# Sheet1.net
KiCad netlist of a schematic drawn in Altium Designer
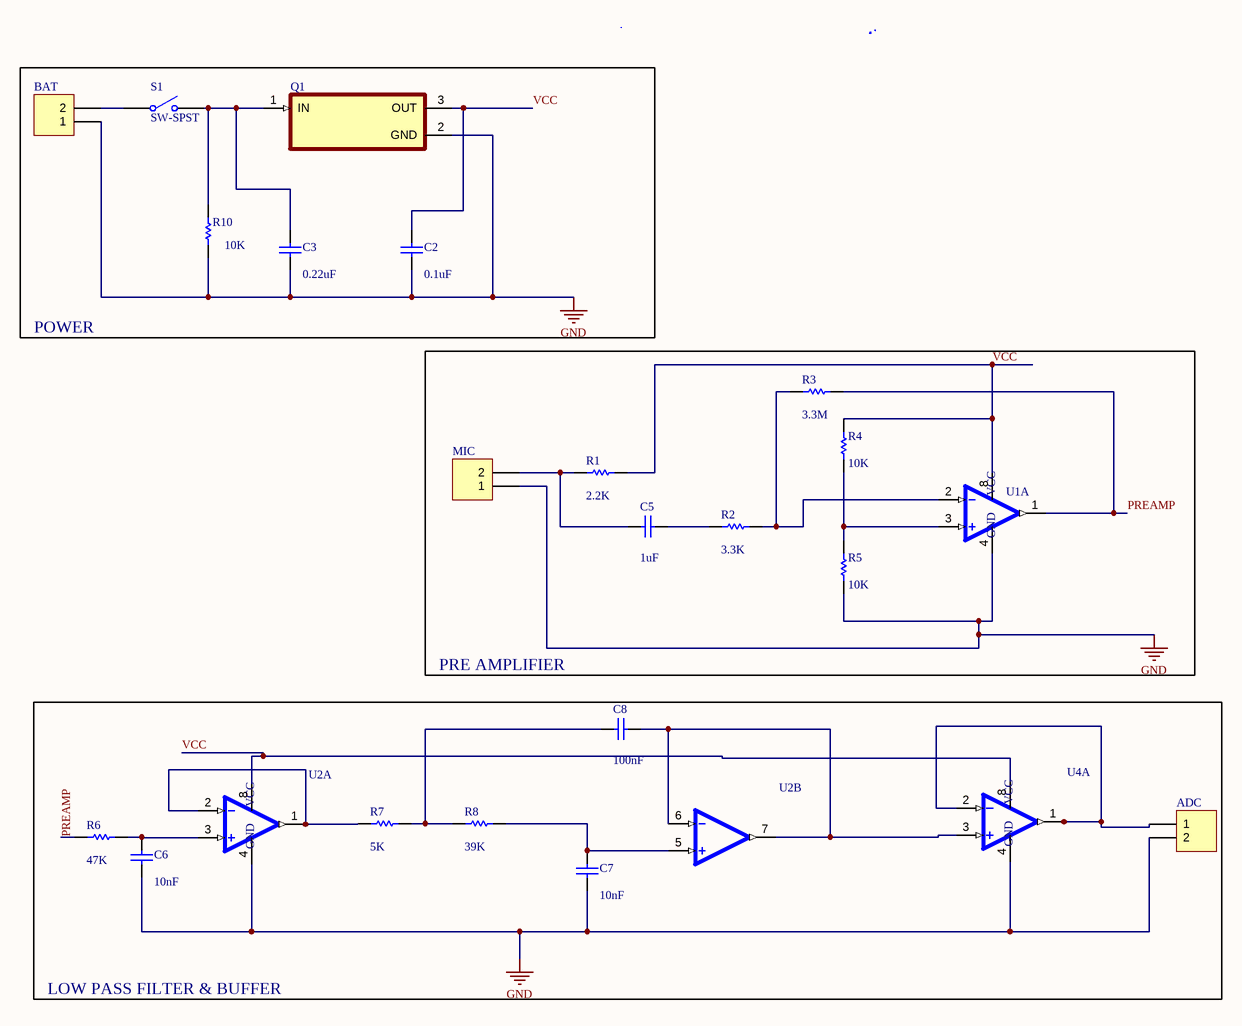
[diagram p0: Sheet1.SchDoc]

(export (version "E")
  (design (tool "Eeschema 10.0.6"))
  (components
    (comp (ref "ADC")
      (value "MHDR1X2")
      (footprint "MHDR1X2")
      (description "Header, 2-Pin")
      (fields (field (name "PUBLISHER") "Altium Limited"))
      (libsource (lib "Miscellaneous Connectors") (part "MHDR1X2"))
    )
    (comp (ref "BAT")
      (value "MHDR1X2")
      (footprint "MHDR1X2")
      (description "Header, 2-Pin")
      (fields (field (name "PUBLISHER") "Altium Limited"))
      (libsource (lib "") (part "MHDR1X2_1"))
    )
    (comp (ref "C2")
      (value "0.1uF")
      (footprint "RAD-0.3")
      (description "Capacitor")
      (fields (field (name "Comment") "Cap") (field (name "PUBLISHER") "Altium Limited"))
      (libsource (lib "Miscellaneous Devices") (part "Cap"))
    )
    (comp (ref "C3")
      (value "0.22uF")
      (footprint "RAD-0.3")
      (description "Capacitor")
      (fields (field (name "Comment") "Cap") (field (name "PUBLISHER") "Altium Limited"))
      (libsource (lib "Miscellaneous Devices") (part "Cap"))
    )
    (comp (ref "C5")
      (value "1uF")
      (footprint "RAD-0.3")
      (description "Capacitor")
      (fields (field (name "Comment") "Cap") (field (name "PUBLISHER") "Altium Limited"))
      (libsource (lib "Miscellaneous Devices") (part "Cap"))
    )
    (comp (ref "C6")
      (value "10nF")
      (footprint "RAD-0.3")
      (description "Capacitor")
      (fields (field (name "Comment") "Cap") (field (name "PUBLISHER") "Altium Limited"))
      (libsource (lib "Miscellaneous Devices") (part "Cap"))
    )
    (comp (ref "C7")
      (value "10nF")
      (footprint "RAD-0.3")
      (description "Capacitor")
      (fields (field (name "Comment") "Cap") (field (name "PUBLISHER") "Altium Limited"))
      (libsource (lib "Miscellaneous Devices") (part "Cap"))
    )
    (comp (ref "C8")
      (value "100nF")
      (footprint "RAD-0.3")
      (description "Capacitor")
      (fields (field (name "Comment") "Cap") (field (name "PUBLISHER") "Altium Limited"))
      (libsource (lib "Miscellaneous Devices") (part "Cap"))
    )
    (comp (ref "MIC")
      (value "MHDR1X2")
      (footprint "MHDR1X2")
      (description "Header, 2-Pin")
      (fields (field (name "PUBLISHER") "Altium Limited"))
      (libsource (lib "") (part "MHDR1X2_1"))
    )
    (comp (ref "Q1")
      (value "LM7805CT/NOPB")
      (footprint "TO254P1054X470X1955-3")
      (libsource (lib "LM7805CT_NOPB") (part "LM7805CT/NOPB"))
    )
    (comp (ref "R1")
      (value "2.2K")
      (footprint "AXIAL-0.3")
      (description "Resistor")
      (fields (field (name "Comment") "Res1") (field (name "PUBLISHER") "Altium Limited"))
      (libsource (lib "Miscellaneous Devices") (part "Res1"))
    )
    (comp (ref "R2")
      (value "3.3K")
      (footprint "AXIAL-0.3")
      (description "Resistor")
      (fields (field (name "Comment") "Res1") (field (name "PUBLISHER") "Altium Limited"))
      (libsource (lib "Miscellaneous Devices") (part "Res1"))
    )
    (comp (ref "R3")
      (value "3.3M")
      (footprint "AXIAL-0.3")
      (description "Resistor")
      (fields (field (name "Comment") "Res1") (field (name "PUBLISHER") "Altium Limited"))
      (libsource (lib "Miscellaneous Devices") (part "Res1"))
    )
    (comp (ref "R4")
      (value "10K")
      (footprint "AXIAL-0.3")
      (description "Resistor")
      (fields (field (name "Comment") "Res1") (field (name "PUBLISHER") "Altium Limited"))
      (libsource (lib "Miscellaneous Devices") (part "Res1"))
    )
    (comp (ref "R5")
      (value "10K")
      (footprint "AXIAL-0.3")
      (description "Resistor")
      (fields (field (name "Comment") "Res1") (field (name "PUBLISHER") "Altium Limited"))
      (libsource (lib "Miscellaneous Devices") (part "Res1"))
    )
    (comp (ref "R6")
      (value "47K")
      (footprint "AXIAL-0.3")
      (description "Resistor")
      (fields (field (name "Comment") "Res1") (field (name "PUBLISHER") "Altium Limited"))
      (libsource (lib "Miscellaneous Devices") (part "Res1"))
    )
    (comp (ref "R7")
      (value "5K")
      (footprint "AXIAL-0.3")
      (description "Resistor")
      (fields (field (name "Comment") "Res1") (field (name "PUBLISHER") "Altium Limited"))
      (libsource (lib "Miscellaneous Devices") (part "Res1"))
    )
    (comp (ref "R8")
      (value "39K")
      (footprint "AXIAL-0.3")
      (description "Resistor")
      (fields (field (name "Comment") "Res1") (field (name "PUBLISHER") "Altium Limited"))
      (libsource (lib "Miscellaneous Devices") (part "Res1"))
    )
    (comp (ref "R10")
      (value "10K")
      (footprint "AXIAL-0.3")
      (description "Resistor")
      (fields (field (name "Comment") "Res1") (field (name "PUBLISHER") "Altium Limited"))
      (libsource (lib "Miscellaneous Devices") (part "Res1"))
    )
    (comp (ref "S1")
      (value "SW-SPST")
      (footprint "SPST-2")
      (description "Single-Pole, Single-Throw Switch")
      (fields (field (name "PUBLISHER") "Altium Limited"))
      (libsource (lib "Miscellaneous Devices") (part "SW-SPST"))
    )
    (comp (ref "U1")
      (value "LM358N")
      (footprint "DIP762W46P254L960H508Q8")
      (description "General Purpose Amplifier 2 Circuit - 8-PDIP")
      (fields (field (name "MF") "onsemi"))
      (libsource (lib "LM358N") (part "LM358N"))
    )
    (comp (ref "U2")
      (value "LM358N")
      (footprint "DIP762W46P254L960H508Q8")
      (description "General Purpose Amplifier 2 Circuit - 8-PDIP")
      (fields (field (name "MF") "onsemi"))
      (libsource (lib "LM358N") (part "LM358N"))
    )
    (comp (ref "U4")
      (value "LM358N")
      (footprint "DIP762W46P254L960H508Q8")
      (description "General Purpose Amplifier 2 Circuit - 8-PDIP")
      (fields (field (name "MF") "onsemi"))
      (libsource (lib "LM358N") (part "LM358N"))
    )
  )
  (nets
    (net (code "1") (name "/PREAMP") (class "Default")
      (node (ref "R3") (pin "2") (pinfunction "2_2") (pintype "passive"))
      (node (ref "R6") (pin "1") (pinfunction "1_1") (pintype "passive"))
      (node (ref "U1") (pin "1") (pinfunction "1OUT_1") (pintype "output"))
    )
    (net (code "2") (name "/VCC") (class "Default")
      (node (ref "C2") (pin "2") (pinfunction "2_2") (pintype "passive"))
      (node (ref "Q1") (pin "3") (pinfunction "OUT_3") (pintype "power_in"))
      (node (ref "R1") (pin "2") (pinfunction "2_2") (pintype "passive"))
      (node (ref "R4") (pin "2") (pinfunction "2_2") (pintype "passive"))
      (node (ref "U1") (pin "8") (pinfunction "VCC_8") (pintype "power_in"))
      (node (ref "U2") (pin "8") (pinfunction "VCC_8") (pintype "power_in"))
      (node (ref "U4") (pin "8") (pinfunction "VCC_8") (pintype "power_in"))
    )
    (net (code "3") (name "GND") (class "Default")
      (node (ref "ADC") (pin "2") (pinfunction "2_2") (pintype "passive"))
      (node (ref "BAT") (pin "1") (pinfunction "1_1") (pintype "passive"))
      (node (ref "C2") (pin "1") (pinfunction "1_1") (pintype "passive"))
      (node (ref "C3") (pin "1") (pinfunction "1_1") (pintype "passive"))
      (node (ref "C6") (pin "2") (pinfunction "2_2") (pintype "passive"))
      (node (ref "C7") (pin "2") (pinfunction "2_2") (pintype "passive"))
      (node (ref "MIC") (pin "1") (pinfunction "1_1") (pintype "passive"))
      (node (ref "Q1") (pin "2") (pinfunction "GND_2") (pintype "power_in"))
      (node (ref "R10") (pin "1") (pinfunction "1_1") (pintype "passive"))
      (node (ref "R5") (pin "1") (pinfunction "1_1") (pintype "passive"))
      (node (ref "U1") (pin "4") (pinfunction "GND_4") (pintype "power_in"))
      (node (ref "U2") (pin "4") (pinfunction "GND_4") (pintype "power_in"))
      (node (ref "U4") (pin "4") (pinfunction "GND_4") (pintype "power_in"))
    )
    (net (code "4") (name "Net-(C5-Pad1)") (class "Default")
      (node (ref "C5") (pin "1") (pinfunction "1_1") (pintype "passive"))
      (node (ref "R2") (pin "1") (pinfunction "1_1") (pintype "passive"))
    )
    (net (code "5") (name "Net-(C5-Pad2)") (class "Default")
      (node (ref "C5") (pin "2") (pinfunction "2_2") (pintype "passive"))
      (node (ref "MIC") (pin "2") (pinfunction "2_2") (pintype "passive"))
      (node (ref "R1") (pin "1") (pinfunction "1_1") (pintype "passive"))
    )
    (net (code "6") (name "Net-(C8-Pad2)") (class "Default")
      (node (ref "C8") (pin "2") (pinfunction "2_2") (pintype "passive"))
      (node (ref "R7") (pin "2") (pinfunction "2_2") (pintype "passive"))
      (node (ref "R8") (pin "1") (pinfunction "1_1") (pintype "passive"))
    )
    (net (code "7") (name "Net-(Q1-IN)") (class "Default")
      (node (ref "C3") (pin "2") (pinfunction "2_2") (pintype "passive"))
      (node (ref "Q1") (pin "1") (pinfunction "IN_1") (pintype "input"))
      (node (ref "R10") (pin "2") (pinfunction "2_2") (pintype "passive"))
      (node (ref "S1") (pin "2") (pinfunction "NO_2") (pintype "passive"))
    )
    (net (code "8") (name "Net-(S1-COMMON)") (class "Default")
      (node (ref "BAT") (pin "2") (pinfunction "2_2") (pintype "passive"))
      (node (ref "S1") (pin "1") (pinfunction "COMMON_1") (pintype "passive"))
    )
    (net (code "9") (name "Net-(U1A-1IN+)") (class "Default")
      (node (ref "R4") (pin "1") (pinfunction "1_1") (pintype "passive"))
      (node (ref "R5") (pin "2") (pinfunction "2_2") (pintype "passive"))
      (node (ref "U1") (pin "3") (pinfunction "1IN+_3") (pintype "input"))
    )
    (net (code "10") (name "Net-(U1A-1IN-)") (class "Default")
      (node (ref "R2") (pin "2") (pinfunction "2_2") (pintype "passive"))
      (node (ref "R3") (pin "1") (pinfunction "1_1") (pintype "passive"))
      (node (ref "U1") (pin "2") (pinfunction "1IN-_2") (pintype "input"))
    )
    (net (code "11") (name "Net-(U2A-1IN+)") (class "Default")
      (node (ref "C6") (pin "1") (pinfunction "1_1") (pintype "passive"))
      (node (ref "R6") (pin "2") (pinfunction "2_2") (pintype "passive"))
      (node (ref "U2") (pin "3") (pinfunction "1IN+_3") (pintype "input"))
    )
    (net (code "12") (name "Net-(U2A-1IN-)") (class "Default")
      (node (ref "R7") (pin "1") (pinfunction "1_1") (pintype "passive"))
      (node (ref "U2") (pin "1") (pinfunction "1OUT_1") (pintype "output"))
      (node (ref "U2") (pin "2") (pinfunction "1IN-_2") (pintype "input"))
    )
    (net (code "13") (name "Net-(U2B-2IN+)") (class "Default")
      (node (ref "C7") (pin "1") (pinfunction "1_1") (pintype "passive"))
      (node (ref "R8") (pin "2") (pinfunction "2_2") (pintype "passive"))
      (node (ref "U2") (pin "5") (pinfunction "2IN+_5") (pintype "input"))
    )
    (net (code "14") (name "Net-(U2B-2IN-)") (class "Default")
      (node (ref "C8") (pin "1") (pinfunction "1_1") (pintype "passive"))
      (node (ref "U2") (pin "6") (pinfunction "2IN-_6") (pintype "input"))
      (node (ref "U2") (pin "7") (pinfunction "2OUT_7") (pintype "output"))
      (node (ref "U4") (pin "3") (pinfunction "1IN+_3") (pintype "input"))
    )
    (net (code "15") (name "Net-(U4A-1IN-)") (class "Default")
      (node (ref "ADC") (pin "1") (pinfunction "1_1") (pintype "passive"))
      (node (ref "U4") (pin "1") (pinfunction "1OUT_1") (pintype "output"))
      (node (ref "U4") (pin "2") (pinfunction "1IN-_2") (pintype "input"))
    )
  )
)
